# LightLink_V4.net
KiCad netlist of a schematic drawn in Altium Designer
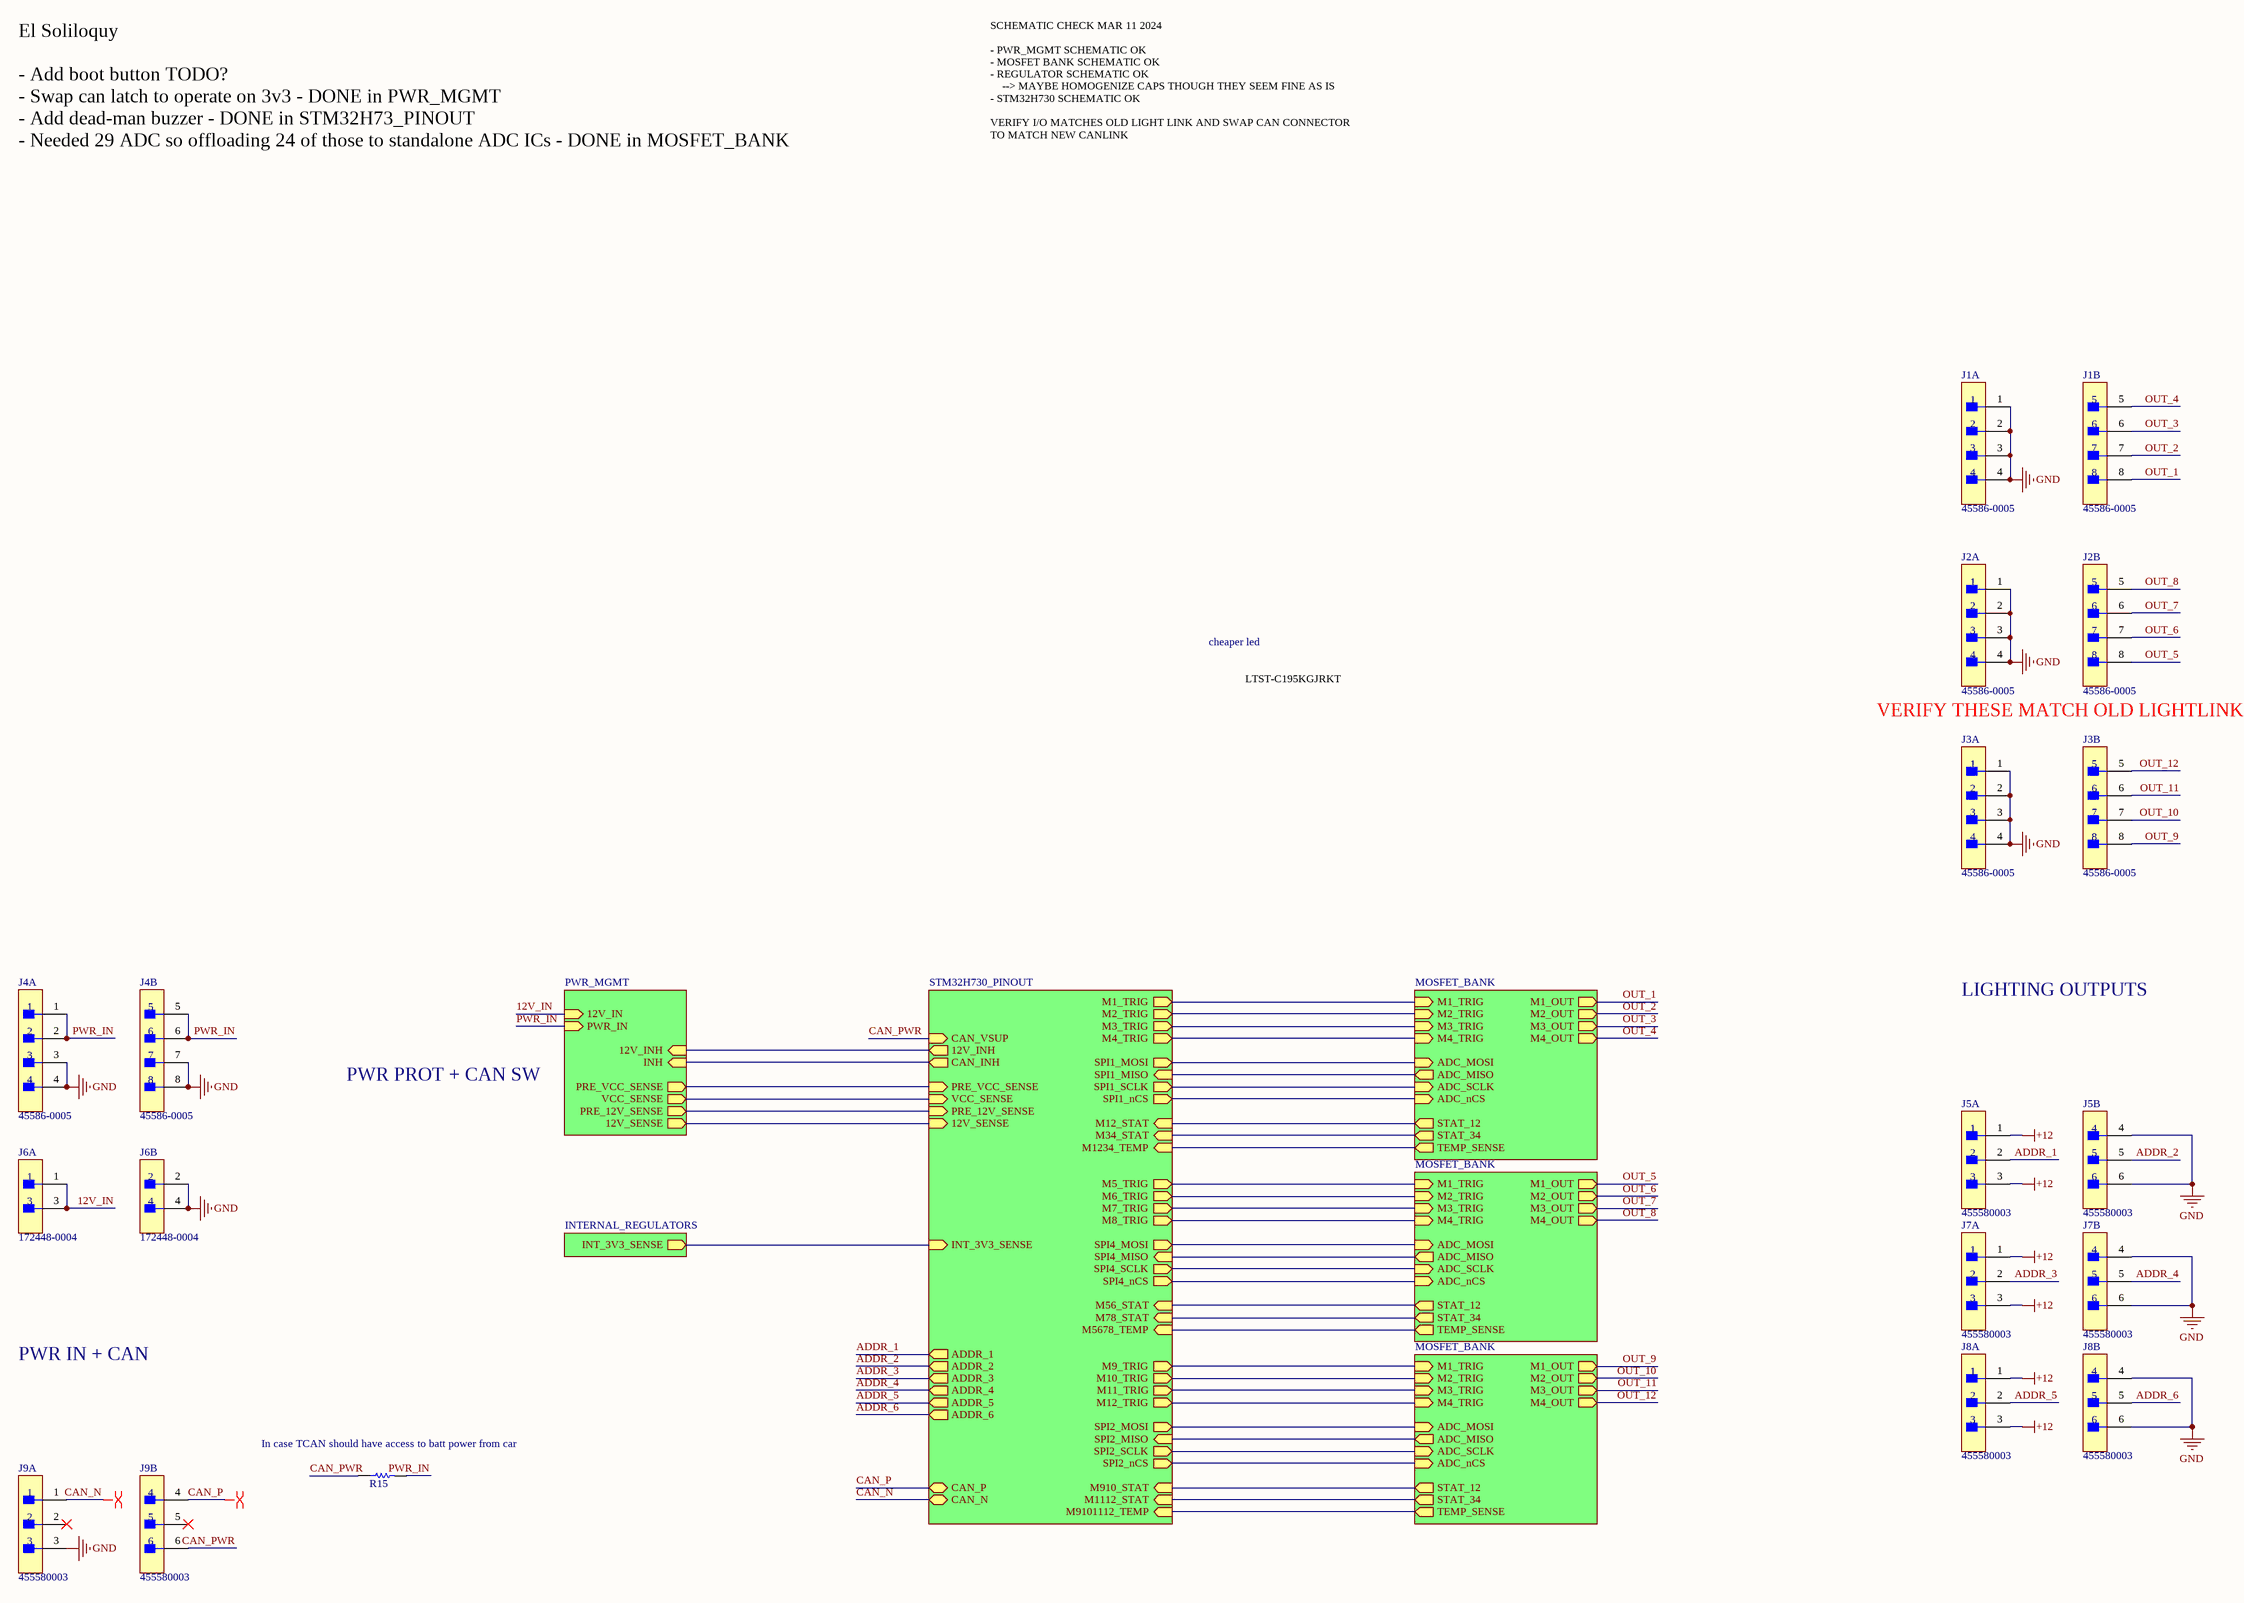
[diagram p0: LightLink_V4.SchDoc]

(export (version "E")
  (design (tool "Eeschema 10.0.6"))
  (components
    (comp (ref "J1")
      (value "45586-0005")
      (footprint "FP-45586-0005-MFG")
      (description "CONN HEADER R/A 8POS 4.2MM")
      (libsource (lib "Altium Content Vault") (part "85438c39ca9ef07d43bb2e97c52bc44"))
    )
    (comp (ref "J2")
      (value "45586-0005")
      (footprint "FP-45586-0005-MFG")
      (description "CONN HEADER R/A 8POS 4.2MM")
      (libsource (lib "Altium Content Vault") (part "85438c39ca9ef07d43bb2e97c52bc44"))
    )
    (comp (ref "J3")
      (value "45586-0005")
      (footprint "FP-45586-0005-MFG")
      (description "CONN HEADER R/A 8POS 4.2MM")
      (libsource (lib "Altium Content Vault") (part "85438c39ca9ef07d43bb2e97c52bc44"))
    )
    (comp (ref "J4")
      (value "45586-0005")
      (footprint "FP-45586-0005-MFG")
      (description "CONN HEADER R/A 8POS 4.2MM")
      (libsource (lib "Altium Content Vault") (part "85438c39ca9ef07d43bb2e97c52bc44"))
    )
    (comp (ref "J5")
      (value "455580003")
      (footprint "FP-455580003-MFG")
      (description "CONN HEADER R/A 6POS 4.2MM")
      (fields
        (field (name "OCTOPART") "https://octopart.com/45558-0003-molex-7672845")
        (field (name "MANUFACTURER") "Molex")
      )
      (libsource (lib "Altium Content Vault") (part "bb9cbdb24149a20ba329b4e86909569"))
    )
    (comp (ref "J6")
      (value "172448-0004")
      (footprint "FP-39-30-1041-MFG")
      (description "Different component but holes should line up. Original P/N is 39-30-1041")
      (fields
        (field (name "MANUFACTURER") "Molex")
        (field (name "OCTOPART") "https://octopart.com/39-30-1041-molex-276737")
      )
      (libsource (lib "Altium Content Vault") (part "1621473add15499e993d6bbd36d0f06"))
    )
    (comp (ref "J7")
      (value "455580003")
      (footprint "FP-455580003-MFG")
      (description "CONN HEADER R/A 6POS 4.2MM")
      (fields
        (field (name "OCTOPART") "https://octopart.com/45558-0003-molex-7672845")
        (field (name "MANUFACTURER") "Molex")
      )
      (libsource (lib "Altium Content Vault") (part "bb9cbdb24149a20ba329b4e86909569"))
    )
    (comp (ref "J8")
      (value "455580003")
      (footprint "FP-455580003-MFG")
      (description "CONN HEADER R/A 6POS 4.2MM")
      (fields
        (field (name "OCTOPART") "https://octopart.com/45558-0003-molex-7672845")
        (field (name "MANUFACTURER") "Molex")
      )
      (libsource (lib "Altium Content Vault") (part "bb9cbdb24149a20ba329b4e86909569"))
    )
    (comp (ref "J9")
      (value "455580003")
      (footprint "FP-455580003-MFG")
      (description "CONN HEADER R/A 6POS 4.2MM")
      (fields
        (field (name "OCTOPART") "https://octopart.com/45558-0003-molex-7672845")
        (field (name "MANUFACTURER") "Molex")
      )
      (libsource (lib "Altium Content Vault") (part "bb9cbdb24149a20ba329b4e86909569"))
    )
    (comp (ref "R15")
      (value "0603 JUMPER")
      (footprint "RESC1609X55X30ML15T15")
      (description "READ THE NAME")
      (libsource (lib "uORocketry Hardware") (part "RES-2"))
    )
  )
  (nets
    (net (code "1") (name "+12") (class "Default")
      (node (ref "J5") (pin "1") (pinfunction "1_1") (pintype "passive"))
      (node (ref "J5") (pin "3") (pinfunction "3_3") (pintype "passive"))
      (node (ref "J7") (pin "1") (pinfunction "1_1") (pintype "passive"))
      (node (ref "J7") (pin "3") (pinfunction "3_3") (pintype "passive"))
      (node (ref "J8") (pin "1") (pinfunction "1_1") (pintype "passive"))
      (node (ref "J8") (pin "3") (pinfunction "3_3") (pintype "passive"))
    )
    (net (code "2") (name "/12V_IN") (class "Default")
      (node (ref "J6") (pin "1") (pinfunction "1_1") (pintype "passive"))
      (node (ref "J6") (pin "3") (pinfunction "3_3") (pintype "passive"))
    )
    (net (code "8") (name "/ADDR_1") (class "Default")
      (node (ref "J5") (pin "2") (pinfunction "2_2") (pintype "passive"))
    )
    (net (code "9") (name "/ADDR_2") (class "Default")
      (node (ref "J5") (pin "5") (pinfunction "5_5") (pintype "passive"))
    )
    (net (code "10") (name "/ADDR_3") (class "Default")
      (node (ref "J7") (pin "2") (pinfunction "2_2") (pintype "passive"))
    )
    (net (code "11") (name "/ADDR_4") (class "Default")
      (node (ref "J7") (pin "5") (pinfunction "5_5") (pintype "passive"))
    )
    (net (code "12") (name "/ADDR_5") (class "Default")
      (node (ref "J8") (pin "2") (pinfunction "2_2") (pintype "passive"))
    )
    (net (code "13") (name "/ADDR_6") (class "Default")
      (node (ref "J8") (pin "5") (pinfunction "5_5") (pintype "passive"))
    )
    (net (code "15") (name "/CAN_N") (class "Default")
      (node (ref "J9") (pin "1") (pinfunction "1_1") (pintype "passive"))
    )
    (net (code "16") (name "/CAN_P") (class "Default")
      (node (ref "J9") (pin "4") (pinfunction "4_4") (pintype "passive"))
    )
    (net (code "17") (name "/CAN_PWR") (class "Default")
      (node (ref "J9") (pin "6") (pinfunction "6_6") (pintype "passive"))
      (node (ref "R15") (pin "1") (pinfunction "1_1") (pintype "passive"))
    )
    (net (code "31") (name "/OUT_1") (class "Default")
      (node (ref "J1") (pin "8") (pinfunction "8_8") (pintype "passive"))
    )
    (net (code "32") (name "/OUT_2") (class "Default")
      (node (ref "J1") (pin "7") (pinfunction "7_7") (pintype "passive"))
    )
    (net (code "33") (name "/OUT_3") (class "Default")
      (node (ref "J1") (pin "6") (pinfunction "6_6") (pintype "passive"))
    )
    (net (code "34") (name "/OUT_4") (class "Default")
      (node (ref "J1") (pin "5") (pinfunction "5_5") (pintype "passive"))
    )
    (net (code "35") (name "/OUT_5") (class "Default")
      (node (ref "J2") (pin "8") (pinfunction "8_8") (pintype "passive"))
    )
    (net (code "36") (name "/OUT_6") (class "Default")
      (node (ref "J2") (pin "7") (pinfunction "7_7") (pintype "passive"))
    )
    (net (code "37") (name "/OUT_7") (class "Default")
      (node (ref "J2") (pin "6") (pinfunction "6_6") (pintype "passive"))
    )
    (net (code "38") (name "/OUT_8") (class "Default")
      (node (ref "J2") (pin "5") (pinfunction "5_5") (pintype "passive"))
    )
    (net (code "39") (name "/OUT_9") (class "Default")
      (node (ref "J3") (pin "8") (pinfunction "8_8") (pintype "passive"))
    )
    (net (code "40") (name "/OUT_10") (class "Default")
      (node (ref "J3") (pin "7") (pinfunction "7_7") (pintype "passive"))
    )
    (net (code "41") (name "/OUT_11") (class "Default")
      (node (ref "J3") (pin "6") (pinfunction "6_6") (pintype "passive"))
    )
    (net (code "42") (name "/OUT_12") (class "Default")
      (node (ref "J3") (pin "5") (pinfunction "5_5") (pintype "passive"))
    )
    (net (code "45") (name "/PWR_IN") (class "Default")
      (node (ref "J4") (pin "1") (pinfunction "1_1") (pintype "passive"))
      (node (ref "J4") (pin "2") (pinfunction "2_2") (pintype "passive"))
      (node (ref "J4") (pin "5") (pinfunction "5_5") (pintype "passive"))
      (node (ref "J4") (pin "6") (pinfunction "6_6") (pintype "passive"))
      (node (ref "R15") (pin "2") (pinfunction "2_2") (pintype "passive"))
    )
    (net (code "65") (name "GND") (class "Default")
      (node (ref "J1") (pin "1") (pinfunction "1_1") (pintype "passive"))
      (node (ref "J1") (pin "2") (pinfunction "2_2") (pintype "passive"))
      (node (ref "J1") (pin "3") (pinfunction "3_3") (pintype "passive"))
      (node (ref "J1") (pin "4") (pinfunction "4_4") (pintype "passive"))
      (node (ref "J2") (pin "1") (pinfunction "1_1") (pintype "passive"))
      (node (ref "J2") (pin "2") (pinfunction "2_2") (pintype "passive"))
      (node (ref "J2") (pin "3") (pinfunction "3_3") (pintype "passive"))
      (node (ref "J2") (pin "4") (pinfunction "4_4") (pintype "passive"))
      (node (ref "J3") (pin "1") (pinfunction "1_1") (pintype "passive"))
      (node (ref "J3") (pin "2") (pinfunction "2_2") (pintype "passive"))
      (node (ref "J3") (pin "3") (pinfunction "3_3") (pintype "passive"))
      (node (ref "J3") (pin "4") (pinfunction "4_4") (pintype "passive"))
      (node (ref "J4") (pin "3") (pinfunction "3_3") (pintype "passive"))
      (node (ref "J4") (pin "4") (pinfunction "4_4") (pintype "passive"))
      (node (ref "J4") (pin "7") (pinfunction "7_7") (pintype "passive"))
      (node (ref "J4") (pin "8") (pinfunction "8_8") (pintype "passive"))
      (node (ref "J5") (pin "4") (pinfunction "4_4") (pintype "passive"))
      (node (ref "J5") (pin "6") (pinfunction "6_6") (pintype "passive"))
      (node (ref "J6") (pin "2") (pinfunction "2_2") (pintype "passive"))
      (node (ref "J6") (pin "4") (pinfunction "4_4") (pintype "passive"))
      (node (ref "J7") (pin "4") (pinfunction "4_4") (pintype "passive"))
      (node (ref "J7") (pin "6") (pinfunction "6_6") (pintype "passive"))
      (node (ref "J8") (pin "4") (pinfunction "4_4") (pintype "passive"))
      (node (ref "J8") (pin "6") (pinfunction "6_6") (pintype "passive"))
      (node (ref "J9") (pin "3") (pinfunction "3_3") (pintype "passive"))
    )
    (net (code "66") (name "unconnected-(J9-Pad2)") (class "Default")
      (node (ref "J9") (pin "2") (pinfunction "2_2") (pintype "passive+no_connect"))
    )
    (net (code "67") (name "unconnected-(J9-Pad5)") (class "Default")
      (node (ref "J9") (pin "5") (pinfunction "5_5") (pintype "passive+no_connect"))
    )
  )
)
